# Encoder.net
KiCad netlist of a schematic drawn in Altium Designer
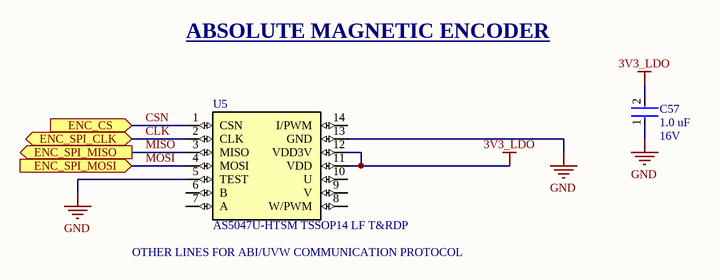
[diagram p0: Encoder.SchDoc]

(export (version "E")
  (design (tool "Eeschema 10.0.6"))
  (components
    (comp (ref "C57")
      (value "CC0603KRX7R7BB105")
      (footprint "CAP-0603")
      (description "CAP CER 1UF 16V X7R 0603")
      (fields (field (name "CAPACITANCE") "1.0 uF") (field (name "VOLTAGE") "16V"))
      (libsource (lib "JLC_25") (part "CAP-1U-0002"))
    )
    (comp (ref "U5")
      (value "AS5047U-HTSM TSSOP14 LF T&RDP")
      (footprint "SOP65P640X110-14N")
      (description "Hall Effect Sensor Rotary Position External Magnet, Not Included Gull Wing")
      (libsource (lib "MasterLib") (part "IC-ABSENC-0001"))
    )
  )
  (nets
    (net (code "1") (name "/CLK") (class "Default")
      (node (ref "U5") (pin "2") (pinfunction "CLK_2") (pintype "bidirectional"))
    )
    (net (code "2") (name "/CSN") (class "Default")
      (node (ref "U5") (pin "1") (pinfunction "CSN_1") (pintype "bidirectional"))
    )
    (net (code "3") (name "/MISO") (class "Default")
      (node (ref "U5") (pin "3") (pinfunction "MISO_3") (pintype "bidirectional"))
    )
    (net (code "4") (name "/MOSI") (class "Default")
      (node (ref "U5") (pin "4") (pinfunction "MOSI_4") (pintype "bidirectional"))
    )
    (net (code "5") (name "3V3_LDO") (class "Default")
      (node (ref "C57") (pin "2") (pinfunction "2_2") (pintype "passive"))
      (node (ref "U5") (pin "11") (pinfunction "VDD_11") (pintype "bidirectional"))
      (node (ref "U5") (pin "12") (pinfunction "VDD3V_12") (pintype "bidirectional"))
    )
    (net (code "6") (name "GND") (class "Default")
      (node (ref "C57") (pin "1") (pinfunction "1_1") (pintype "passive"))
      (node (ref "U5") (pin "13") (pinfunction "GND_13") (pintype "bidirectional"))
      (node (ref "U5") (pin "5") (pinfunction "TEST_5") (pintype "bidirectional"))
    )
    (net (code "7") (name "unconnected-(U5-A-Pad7)") (class "Default")
      (node (ref "U5") (pin "7") (pinfunction "A_7") (pintype "bidirectional"))
    )
    (net (code "8") (name "unconnected-(U5-B-Pad6)") (class "Default")
      (node (ref "U5") (pin "6") (pinfunction "B_6") (pintype "bidirectional"))
    )
    (net (code "9") (name "unconnected-(U5-I{slash}PWM-Pad14)") (class "Default")
      (node (ref "U5") (pin "14") (pinfunction "I/PWM_14") (pintype "bidirectional"))
    )
    (net (code "10") (name "unconnected-(U5-U-Pad10)") (class "Default")
      (node (ref "U5") (pin "10") (pinfunction "U_10") (pintype "bidirectional"))
    )
    (net (code "11") (name "unconnected-(U5-V-Pad9)") (class "Default")
      (node (ref "U5") (pin "9") (pinfunction "V_9") (pintype "bidirectional"))
    )
    (net (code "12") (name "unconnected-(U5-W{slash}PWM-Pad8)") (class "Default")
      (node (ref "U5") (pin "8") (pinfunction "W/PWM_8") (pintype "bidirectional"))
    )
  )
)
